# PCIe.net
KiCad netlist of a schematic drawn in Altium Designer
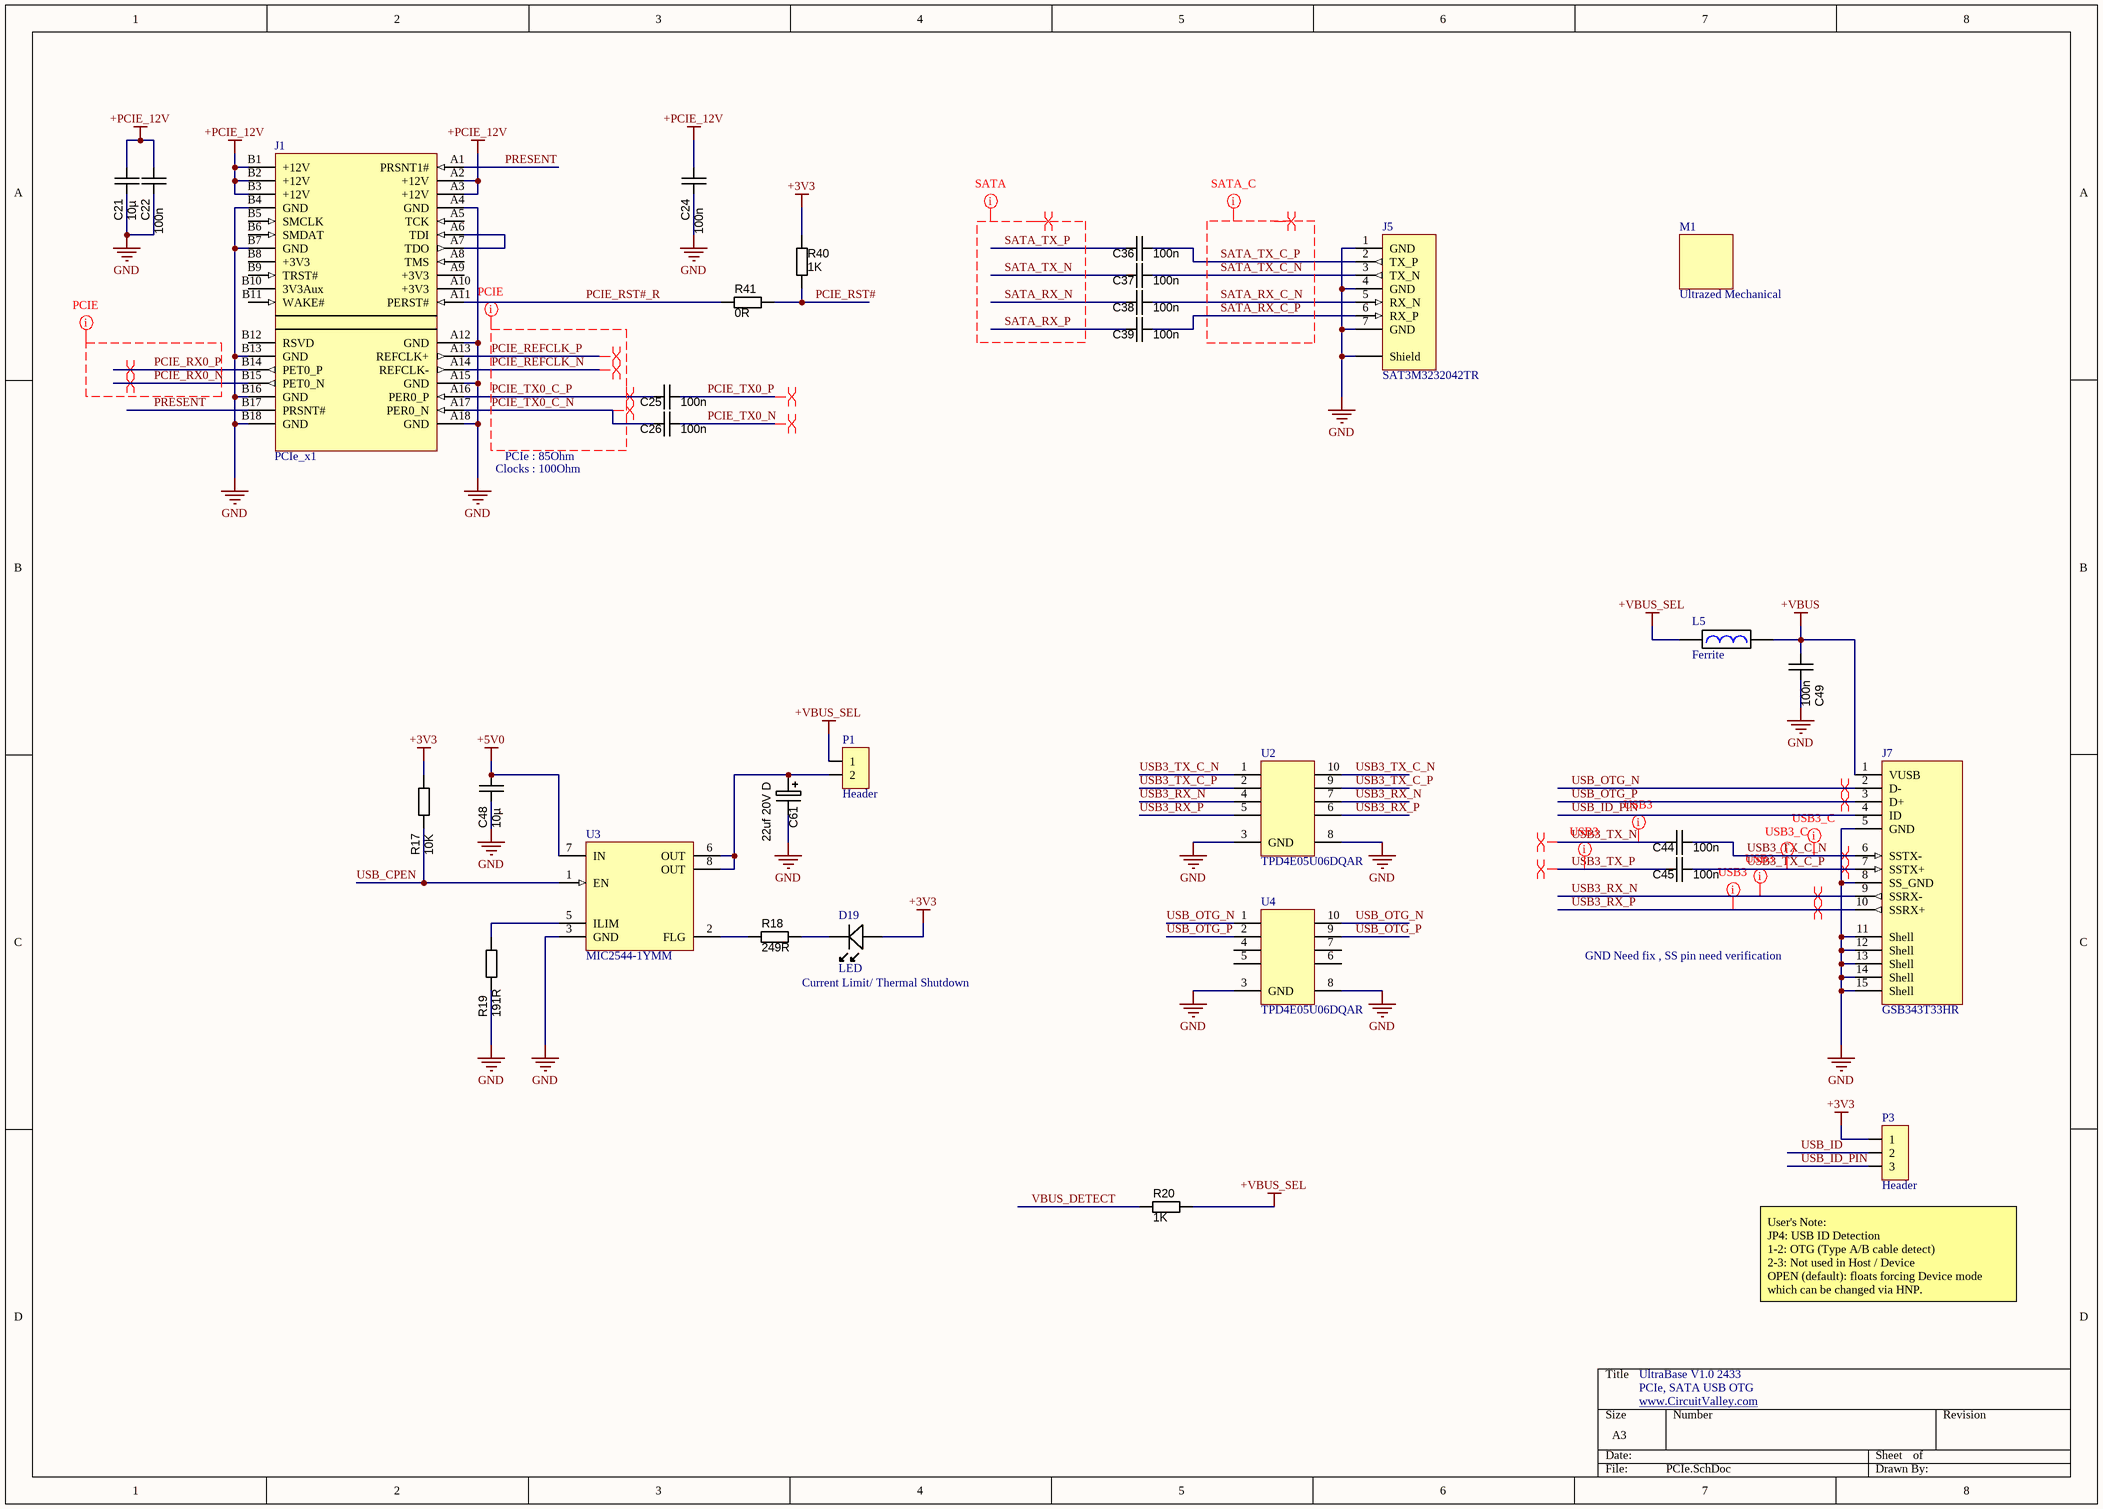
[diagram p0: PCIe.SchDoc]

(export (version "E")
  (design (tool "Eeschema 10.0.6"))
  (components
    (comp (ref "C21")
      (value "10µ")
      (footprint "CAPC3225N")
      (description "Capacitor SMD Cer 10uF 20% 16V X5R 1210")
      (fields (field (name "TOLERANCE") "±20%"))
      (libsource (lib "PBL - Capacitors") (part "CAPC_10u_1210_50V"))
    )
    (comp (ref "C22")
      (value "100n")
      (footprint "CAPC1608N")
      (description "Capacitor SMD Cer 120pF 10% 50V C0G 0603")
      (fields (field (name "TOLERANCE") "±10%"))
      (libsource (lib "PBL - Capacitors") (part "CAPC_120p_0603_C0G_50V"))
    )
    (comp (ref "C24")
      (value "100n")
      (footprint "CAPC1608N")
      (description "Capacitor SMD Cer 120pF 10% 50V C0G 0603")
      (fields (field (name "TOLERANCE") "±10%"))
      (libsource (lib "PBL - Capacitors") (part "CAPC_120p_0603_C0G_50V"))
    )
    (comp (ref "C25")
      (value "100n")
      (footprint "CAPC1005N")
      (description "Capacitor SMD Cer 100nF 10% 16V X5R 0402")
      (fields (field (name "TOLERANCE") "±10%"))
      (libsource (lib "PBL - Capacitors") (part "CAPC_100n_0402_16V_10%"))
    )
    (comp (ref "C26")
      (value "100n")
      (footprint "CAPC1005N")
      (description "Capacitor SMD Cer 100nF 10% 16V X5R 0402")
      (fields (field (name "TOLERANCE") "±10%"))
      (libsource (lib "PBL - Capacitors") (part "CAPC_100n_0402_16V_10%"))
    )
    (comp (ref "C36")
      (value "100n")
      (footprint "CAPC1005N")
      (description "Capacitor SMD Cer 100nF 10% 16V X5R 0402")
      (fields (field (name "TOLERANCE") "±10%"))
      (libsource (lib "PBL - Capacitors") (part "CAPC_100n_0402_16V_10%"))
    )
    (comp (ref "C37")
      (value "100n")
      (footprint "CAPC1005N")
      (description "Capacitor SMD Cer 100nF 10% 16V X5R 0402")
      (fields (field (name "TOLERANCE") "±10%"))
      (libsource (lib "PBL - Capacitors") (part "CAPC_100n_0402_16V_10%"))
    )
    (comp (ref "C38")
      (value "100n")
      (footprint "CAPC1005N")
      (description "Capacitor SMD Cer 100nF 10% 16V X5R 0402")
      (fields (field (name "TOLERANCE") "±10%"))
      (libsource (lib "PBL - Capacitors") (part "CAPC_100n_0402_16V_10%"))
    )
    (comp (ref "C39")
      (value "100n")
      (footprint "CAPC1005N")
      (description "Capacitor SMD Cer 100nF 10% 16V X5R 0402")
      (fields (field (name "TOLERANCE") "±10%"))
      (libsource (lib "PBL - Capacitors") (part "CAPC_100n_0402_16V_10%"))
    )
    (comp (ref "C44")
      (value "100n")
      (footprint "CAPC1005N")
      (description "Capacitor SMD Cer 100nF 10% 16V X5R 0402")
      (fields (field (name "TOLERANCE") "±10%"))
      (libsource (lib "PBL - Capacitors") (part "CAPC_100n_0402_16V_10%"))
    )
    (comp (ref "C45")
      (value "100n")
      (footprint "CAPC1005N")
      (description "Capacitor SMD Cer 100nF 10% 16V X5R 0402")
      (fields (field (name "TOLERANCE") "±10%"))
      (libsource (lib "PBL - Capacitors") (part "CAPC_100n_0402_16V_10%"))
    )
    (comp (ref "C48")
      (value "10µ")
      (footprint "CAPC3225N")
      (description "Capacitor SMD Cer 10uF 20% 16V X5R 1210")
      (fields (field (name "TOLERANCE") "±20%"))
      (libsource (lib "PBL - Capacitors") (part "CAPC_10u_1210_50V"))
    )
    (comp (ref "C49")
      (value "100n")
      (footprint "CAPC1608N")
      (description "Capacitor SMD Cer 120pF 10% 50V C0G 0603")
      (fields (field (name "TOLERANCE") "±10%"))
      (libsource (lib "PBL - Capacitors") (part "CAPC_120p_0603_C0G_50V"))
    )
    (comp (ref "C61")
      (value "22uf 20V D")
      (footprint "CAPMP7343X310N")
      (description "Capacitor SMD Tant 330uF 20% 6V3 2917")
      (fields
        (field (name "TOLERANCE") "±20%")
        (field (name "MANUFACTURER PART NUMBER") "T520D337M006ATE015")
      )
      (libsource (lib "PBL - Capacitors") (part "CAPT_330u_2917_6V3"))
    )
    (comp (ref "D19") (value "LED") (footprint "1206_LED") (libsource (lib "cvlib") (part "LED")))
    (comp (ref "J1")
      (value "PCIe_x1")
      (footprint "PCIe_x1")
      (description "PCIe X1 Card edge")
      (libsource (lib "cvlib") (part "PCIe_x1"))
    )
    (comp (ref "J5")
      (value "SAT3M3232042TR")
      (footprint "SAT3M3232042TR")
      (description "Sata Connector Vertical")
      (libsource (lib "cvlib") (part "SAT3M3232042TR"))
    )
    (comp (ref "J7")
      (value "GSB343T33HR")
      (footprint "GSB343T33HR")
      (description "USB3.2 Micro B")
      (libsource (lib "cvlib") (part "GSB343T33HR"))
    )
    (comp (ref "L5")
      (value "Ferrite")
      (footprint "FBC2012N")
      (description "Ferrite Bead")
      (libsource (lib "cvlib") (part "Ferrite Bead"))
    )
    (comp (ref "M1")
      (value "Ultrazed Mechanical")
      (footprint "ULTRAZED_SOM_Mechanical")
      (libsource (lib "cvlib") (part "UltrazedSOMMechanical"))
    )
    (comp (ref "P1")
      (value "Header")
      (footprint "Header2x")
      (description "2 Pin Header")
      (libsource (lib "cvlib") (part "Header_2Pin"))
    )
    (comp (ref "P3")
      (value "Header")
      (footprint "Header3x")
      (description "3 Pin Header")
      (libsource (lib "cvlib") (part "Header_3Pin"))
    )
    (comp (ref "R17")
      (value "10K")
      (footprint "RESC1608N")
      (description "Resistor, SMD chip")
      (fields (field (name "TOLERANCE") "±5%") (field (name "Comment") "RES_NL_0603"))
      (libsource (lib "") (part "RES_NL_0603_2"))
    )
    (comp (ref "R18")
      (value "249R")
      (footprint "RESC1608N")
      (description "Resistor, SMD chip")
      (fields (field (name "TOLERANCE") "±5%") (field (name "Comment") "RES_NL_0603"))
      (libsource (lib "") (part "RES_NL_0603_1"))
    )
    (comp (ref "R19")
      (value "191R")
      (footprint "RESC1608N")
      (description "Resistor, SMD chip")
      (fields (field (name "TOLERANCE") "±5%") (field (name "Comment") "RES_NL_0603"))
      (libsource (lib "") (part "RES_NL_0603_2"))
    )
    (comp (ref "R20")
      (value "1K")
      (footprint "RESC1608N")
      (description "Resistor, SMD chip")
      (fields (field (name "TOLERANCE") "±5%") (field (name "Comment") "RES_NL_0603"))
      (libsource (lib "") (part "RES_NL_0603_1"))
    )
    (comp (ref "R40")
      (value "1K")
      (footprint "RESC1608N")
      (description "Resistor, SMD chip")
      (fields (field (name "TOLERANCE") "±5%") (field (name "Comment") "RES_NL_0603"))
      (libsource (lib "PBL - Resistors") (part "RES_NL_0603"))
    )
    (comp (ref "R41")
      (value "0R")
      (footprint "RESC1608N")
      (description "Resistor, SMD chip")
      (fields (field (name "TOLERANCE") "±5%") (field (name "Comment") "RES_NL_0603"))
      (libsource (lib "") (part "RES_NL_0603_1"))
    )
    (comp (ref "U2")
      (value "TPD4E05U06DQAR")
      (footprint "uDFN-10")
      (description "ESD Protection")
      (libsource (lib "cvlib") (part "TPD4E05U06DQAR"))
    )
    (comp (ref "U3")
      (value "MIC2544-1YMM")
      (footprint "MSOP8")
      (description "High Side Switch, Current limit programmable")
      (libsource (lib "cvlib") (part "MIC2544"))
    )
    (comp (ref "U4")
      (value "TPD4E05U06DQAR")
      (footprint "uDFN-10")
      (description "ESD Protection")
      (libsource (lib "cvlib") (part "TPD4E05U06DQAR"))
    )
  )
  (nets
    (net (code "1") (name "+3V3") (class "Default")
      (node (ref "D19") (pin "A") (pinfunction "A_A") (pintype "passive"))
      (node (ref "P3") (pin "1") (pinfunction "1_1") (pintype "passive"))
      (node (ref "R17") (pin "1") (pinfunction "1_1") (pintype "passive"))
      (node (ref "R40") (pin "2") (pinfunction "2_2") (pintype "passive"))
    )
    (net (code "2") (name "+5V0") (class "Default")
      (node (ref "C48") (pin "1") (pintype "passive"))
      (node (ref "U3") (pin "7") (pinfunction "IN_7") (pintype "passive"))
    )
    (net (code "3") (name "+PCIE_12V") (class "Default")
      (node (ref "C21") (pin "1") (pintype "passive"))
      (node (ref "C22") (pin "1") (pintype "passive"))
      (node (ref "C24") (pin "1") (pintype "passive"))
      (node (ref "J1") (pin "A2") (pinfunction "+12V_A2") (pintype "power_in"))
      (node (ref "J1") (pin "A3") (pinfunction "+12V_A3") (pintype "power_in"))
      (node (ref "J1") (pin "B1") (pinfunction "+12V_B1") (pintype "power_in"))
      (node (ref "J1") (pin "B2") (pinfunction "+12V_B2") (pintype "power_in"))
      (node (ref "J1") (pin "B3") (pinfunction "+12V_B3") (pintype "power_in"))
    )
    (net (code "4") (name "+VBUS") (class "Default")
      (node (ref "C49") (pin "1") (pintype "passive"))
      (node (ref "J7") (pin "1") (pinfunction "VUSB_1") (pintype "passive"))
      (node (ref "L5") (pin "2") (pinfunction "2_2") (pintype "passive"))
    )
    (net (code "5") (name "+VBUS_SEL") (class "Default")
      (node (ref "L5") (pin "1") (pinfunction "1_1") (pintype "passive"))
      (node (ref "P1") (pin "1") (pinfunction "1_1") (pintype "passive"))
      (node (ref "R20") (pin "2") (pinfunction "2_2") (pintype "passive"))
    )
    (net (code "6") (name "/PCIE_REFCLK_N") (class "Default")
      (node (ref "J1") (pin "A14") (pinfunction "REFCLK-_A14") (pintype "output"))
    )
    (net (code "7") (name "/PCIE_REFCLK_P") (class "Default")
      (node (ref "J1") (pin "A13") (pinfunction "REFCLK+_A13") (pintype "output"))
    )
    (net (code "8") (name "/PCIE_RST#") (class "Default")
      (node (ref "R40") (pin "1") (pinfunction "1_1") (pintype "passive"))
      (node (ref "R41") (pin "2") (pinfunction "2_2") (pintype "passive"))
    )
    (net (code "9") (name "/PCIE_RST#_R") (class "Default")
      (node (ref "J1") (pin "A11") (pinfunction "PERST#_A11") (pintype "input"))
      (node (ref "R41") (pin "1") (pinfunction "1_1") (pintype "passive"))
    )
    (net (code "10") (name "/PCIE_RX0_N") (class "Default")
      (node (ref "J1") (pin "B15") (pinfunction "PET0_N_B15") (pintype "output"))
    )
    (net (code "11") (name "/PCIE_RX0_P") (class "Default")
      (node (ref "J1") (pin "B14") (pinfunction "PET0_P_B14") (pintype "output"))
    )
    (net (code "12") (name "/PCIE_TX0_C_N") (class "Default")
      (node (ref "C26") (pin "1") (pintype "passive"))
      (node (ref "J1") (pin "A17") (pinfunction "PER0_N_A17") (pintype "input"))
    )
    (net (code "13") (name "/PCIE_TX0_C_P") (class "Default")
      (node (ref "C25") (pin "1") (pintype "passive"))
      (node (ref "J1") (pin "A16") (pinfunction "PER0_P_A16") (pintype "input"))
    )
    (net (code "14") (name "/PCIE_TX0_N") (class "Default") (node (ref "C26") (pin "2") (pintype "passive")))
    (net (code "15") (name "/PCIE_TX0_P") (class "Default") (node (ref "C25") (pin "2") (pintype "passive")))
    (net (code "16") (name "/PRESENT") (class "Default")
      (node (ref "J1") (pin "A1") (pinfunction "PRSNT1#_A1") (pintype "input"))
      (node (ref "J1") (pin "B17") (pinfunction "PRSNT#_B17") (pintype "power_in"))
    )
    (net (code "17") (name "/SATA_RX_C_N") (class "Default")
      (node (ref "C38") (pin "2") (pintype "passive"))
      (node (ref "J5") (pin "5") (pinfunction "RX_N_5") (pintype "input"))
    )
    (net (code "18") (name "/SATA_RX_C_P") (class "Default")
      (node (ref "C39") (pin "2") (pintype "passive"))
      (node (ref "J5") (pin "6") (pinfunction "RX_P_6") (pintype "input"))
    )
    (net (code "19") (name "/SATA_RX_N") (class "Default") (node (ref "C38") (pin "1") (pintype "passive")))
    (net (code "20") (name "/SATA_RX_P") (class "Default") (node (ref "C39") (pin "1") (pintype "passive")))
    (net (code "21") (name "/SATA_TX_C_N") (class "Default")
      (node (ref "C37") (pin "2") (pintype "passive"))
      (node (ref "J5") (pin "3") (pinfunction "TX_N_3") (pintype "output"))
    )
    (net (code "22") (name "/SATA_TX_C_P") (class "Default")
      (node (ref "C36") (pin "2") (pintype "passive"))
      (node (ref "J5") (pin "2") (pinfunction "TX_P_2") (pintype "output"))
    )
    (net (code "23") (name "/SATA_TX_N") (class "Default") (node (ref "C37") (pin "1") (pintype "passive")))
    (net (code "24") (name "/SATA_TX_P") (class "Default") (node (ref "C36") (pin "1") (pintype "passive")))
    (net (code "25") (name "/USB3_RX_N") (class "Default")
      (node (ref "J7") (pin "9") (pinfunction "SSRX-_9") (pintype "output"))
      (node (ref "U2") (pin "4") (pintype "passive"))
      (node (ref "U2") (pin "7") (pintype "passive"))
    )
    (net (code "26") (name "/USB3_RX_P") (class "Default")
      (node (ref "J7") (pin "10") (pinfunction "SSRX+_10") (pintype "output"))
      (node (ref "U2") (pin "5") (pintype "passive"))
      (node (ref "U2") (pin "6") (pintype "passive"))
    )
    (net (code "27") (name "/USB3_TX_C_N") (class "Default")
      (node (ref "C44") (pin "2") (pintype "passive"))
      (node (ref "J7") (pin "6") (pinfunction "SSTX-_6") (pintype "input"))
      (node (ref "U2") (pin "1") (pintype "passive"))
      (node (ref "U2") (pin "10") (pintype "passive"))
    )
    (net (code "28") (name "/USB3_TX_C_P") (class "Default")
      (node (ref "C45") (pin "2") (pintype "passive"))
      (node (ref "J7") (pin "7") (pinfunction "SSTX+_7") (pintype "input"))
      (node (ref "U2") (pin "2") (pintype "passive"))
      (node (ref "U2") (pin "9") (pintype "passive"))
    )
    (net (code "29") (name "/USB3_TX_N") (class "Default") (node (ref "C44") (pin "1") (pintype "passive")))
    (net (code "30") (name "/USB3_TX_P") (class "Default") (node (ref "C45") (pin "1") (pintype "passive")))
    (net (code "31") (name "/USB_CPEN") (class "Default")
      (node (ref "R17") (pin "2") (pinfunction "2_2") (pintype "passive"))
      (node (ref "U3") (pin "1") (pinfunction "EN_1") (pintype "input"))
    )
    (net (code "32") (name "/USB_ID") (class "Default")
      (node (ref "P3") (pin "2") (pinfunction "2_2") (pintype "passive"))
    )
    (net (code "33") (name "/USB_ID_PIN") (class "Default")
      (node (ref "J7") (pin "4") (pinfunction "ID_4") (pintype "passive"))
      (node (ref "P3") (pin "3") (pinfunction "3_3") (pintype "passive"))
    )
    (net (code "34") (name "/USB_OTG_N") (class "Default")
      (node (ref "J7") (pin "2") (pinfunction "D-_2") (pintype "passive"))
      (node (ref "U4") (pin "1") (pintype "passive"))
      (node (ref "U4") (pin "10") (pintype "passive"))
    )
    (net (code "35") (name "/USB_OTG_P") (class "Default")
      (node (ref "J7") (pin "3") (pinfunction "D+_3") (pintype "passive"))
      (node (ref "U4") (pin "2") (pintype "passive"))
      (node (ref "U4") (pin "9") (pintype "passive"))
    )
    (net (code "36") (name "/VBUS_DETECT") (class "Default")
      (node (ref "R20") (pin "1") (pinfunction "1_1") (pintype "passive"))
    )
    (net (code "37") (name "GND") (class "Default")
      (node (ref "C21") (pin "2") (pintype "passive"))
      (node (ref "C22") (pin "2") (pintype "passive"))
      (node (ref "C24") (pin "2") (pintype "passive"))
      (node (ref "C48") (pin "2") (pintype "passive"))
      (node (ref "C49") (pin "2") (pintype "passive"))
      (node (ref "C61") (pin "2") (pintype "passive"))
      (node (ref "J1") (pin "A12") (pinfunction "GND_A12") (pintype "power_in"))
      (node (ref "J1") (pin "A15") (pinfunction "GND_A15") (pintype "power_in"))
      (node (ref "J1") (pin "A18") (pinfunction "GND_A18") (pintype "power_in"))
      (node (ref "J1") (pin "A4") (pinfunction "GND_A4") (pintype "power_in"))
      (node (ref "J1") (pin "B13") (pinfunction "GND_B13") (pintype "power_in"))
      (node (ref "J1") (pin "B16") (pinfunction "GND_B16") (pintype "power_in"))
      (node (ref "J1") (pin "B18") (pinfunction "GND_B18") (pintype "power_in"))
      (node (ref "J1") (pin "B4") (pinfunction "GND_B4") (pintype "power_in"))
      (node (ref "J1") (pin "B7") (pinfunction "GND_B7") (pintype "power_in"))
      (node (ref "J5") (pin "1") (pinfunction "GND_1") (pintype "passive"))
      (node (ref "J5") (pin "4") (pinfunction "GND_4") (pintype "passive"))
      (node (ref "J5") (pin "7") (pinfunction "GND_7") (pintype "passive"))
      (node (ref "J5") (pin "SH") (pinfunction "Shield_SH") (pintype "passive"))
      (node (ref "J7") (pin "11") (pinfunction "Shell_11") (pintype "passive"))
      (node (ref "J7") (pin "12") (pinfunction "Shell_12") (pintype "passive"))
      (node (ref "J7") (pin "13") (pinfunction "Shell_13") (pintype "passive"))
      (node (ref "J7") (pin "14") (pinfunction "Shell_14") (pintype "passive"))
      (node (ref "J7") (pin "15") (pinfunction "Shell_15") (pintype "passive"))
      (node (ref "J7") (pin "5") (pinfunction "GND_5") (pintype "passive"))
      (node (ref "J7") (pin "8") (pinfunction "SS_GND_8") (pintype "passive"))
      (node (ref "R19") (pin "2") (pinfunction "2_2") (pintype "passive"))
      (node (ref "U2") (pin "3") (pinfunction "GND_3") (pintype "passive"))
      (node (ref "U2") (pin "8") (pinfunction "GND_8") (pintype "passive"))
      (node (ref "U3") (pin "3") (pinfunction "GND_3") (pintype "passive"))
      (node (ref "U4") (pin "3") (pinfunction "GND_3") (pintype "passive"))
      (node (ref "U4") (pin "8") (pinfunction "GND_8") (pintype "passive"))
    )
    (net (code "38") (name "Net-(C61-Pad1)") (class "Default")
      (node (ref "C61") (pin "1") (pintype "passive"))
      (node (ref "P1") (pin "2") (pinfunction "2_2") (pintype "passive"))
      (node (ref "U3") (pin "6") (pinfunction "OUT_6") (pintype "passive"))
      (node (ref "U3") (pin "8") (pinfunction "OUT_8") (pintype "passive"))
    )
    (net (code "39") (name "Net-(D19-PadK)") (class "Default")
      (node (ref "D19") (pin "K") (pinfunction "K_K") (pintype "passive"))
      (node (ref "R18") (pin "2") (pinfunction "2_2") (pintype "passive"))
    )
    (net (code "40") (name "Net-(J1-TDI)") (class "Default")
      (node (ref "J1") (pin "A6") (pinfunction "TDI_A6") (pintype "input"))
      (node (ref "J1") (pin "A7") (pinfunction "TDO_A7") (pintype "output"))
    )
    (net (code "41") (name "Net-(U3-FLG)") (class "Default")
      (node (ref "R18") (pin "1") (pinfunction "1_1") (pintype "passive"))
      (node (ref "U3") (pin "2") (pinfunction "FLG_2") (pintype "open_collector"))
    )
    (net (code "42") (name "Net-(U3-ILIM)") (class "Default")
      (node (ref "R19") (pin "1") (pinfunction "1_1") (pintype "passive"))
      (node (ref "U3") (pin "5") (pinfunction "ILIM_5") (pintype "passive"))
    )
    (net (code "43") (name "unconnected-(J1-+3V3-PadA9)") (class "Default")
      (node (ref "J1") (pin "A9") (pinfunction "+3V3_A9") (pintype "power_in"))
    )
    (net (code "44") (name "unconnected-(J1-+3V3-PadA10)") (class "Default")
      (node (ref "J1") (pin "A10") (pinfunction "+3V3_A10") (pintype "power_in"))
    )
    (net (code "45") (name "unconnected-(J1-+3V3-PadB8)") (class "Default")
      (node (ref "J1") (pin "B8") (pinfunction "+3V3_B8") (pintype "power_in"))
    )
    (net (code "46") (name "unconnected-(J1-3V3Aux-PadB10)") (class "Default")
      (node (ref "J1") (pin "B10") (pinfunction "3V3Aux_B10") (pintype "power_in"))
    )
    (net (code "47") (name "unconnected-(J1-RSVD-PadB12)") (class "Default")
      (node (ref "J1") (pin "B12") (pinfunction "RSVD_B12") (pintype "power_in"))
    )
    (net (code "48") (name "unconnected-(J1-SMCLK-PadB5)") (class "Default")
      (node (ref "J1") (pin "B5") (pinfunction "SMCLK_B5") (pintype "input"))
    )
    (net (code "49") (name "unconnected-(J1-SMDAT-PadB6)") (class "Default")
      (node (ref "J1") (pin "B6") (pinfunction "SMDAT_B6") (pintype "input"))
    )
    (net (code "50") (name "unconnected-(J1-TCK-PadA5)") (class "Default")
      (node (ref "J1") (pin "A5") (pinfunction "TCK_A5") (pintype "input"))
    )
    (net (code "51") (name "unconnected-(J1-TMS-PadA8)") (class "Default")
      (node (ref "J1") (pin "A8") (pinfunction "TMS_A8") (pintype "input"))
    )
    (net (code "52") (name "unconnected-(J1-TRST#-PadB9)") (class "Default")
      (node (ref "J1") (pin "B9") (pinfunction "TRST#_B9") (pintype "input"))
    )
    (net (code "53") (name "unconnected-(J1-WAKE#-PadB11)") (class "Default")
      (node (ref "J1") (pin "B11") (pinfunction "WAKE#_B11") (pintype "input"))
    )
    (net (code "54") (name "unconnected-(U4-Pad4)") (class "Default")
      (node (ref "U4") (pin "4") (pintype "passive"))
    )
    (net (code "55") (name "unconnected-(U4-Pad5)") (class "Default")
      (node (ref "U4") (pin "5") (pintype "passive"))
    )
    (net (code "56") (name "unconnected-(U4-Pad6)") (class "Default")
      (node (ref "U4") (pin "6") (pintype "passive"))
    )
    (net (code "57") (name "unconnected-(U4-Pad7)") (class "Default")
      (node (ref "U4") (pin "7") (pintype "passive"))
    )
  )
)
